# HM_Nightfall-mini-2e_Encoder-PCB-L_v1.net
KiCad netlist of a schematic drawn in EAGLE
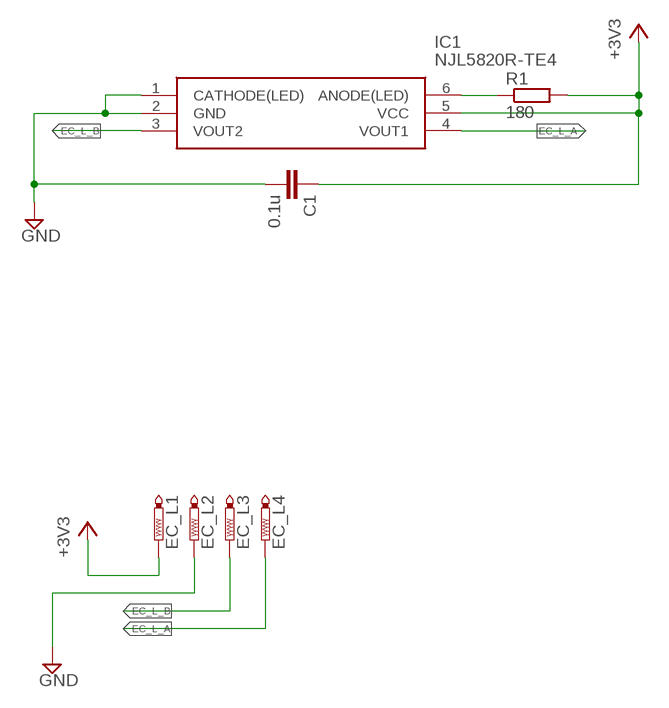
[diagram p0: schematic, sheet 1]

(export (version "E")
  (design (tool "Eeschema 10.0.6"))
  (components
    (comp (ref "C1")
      (value "0.1u")
      (footprint "eagle-import:C0402")
      (libsource (lib "eagle-import") (part "C-EUC0402"))
    )
    (comp (ref "EC_L1")
      (value "PTR1TP06SQ")
      (footprint "eagle-import:TP06SQ")
      (libsource (lib "eagle-import") (part "PTR1TP06SQ"))
    )
    (comp (ref "EC_L2")
      (value "PTR1TP06SQ")
      (footprint "eagle-import:TP06SQ")
      (libsource (lib "eagle-import") (part "PTR1TP06SQ"))
    )
    (comp (ref "EC_L3")
      (value "PTR1TP06SQ")
      (footprint "eagle-import:TP06SQ")
      (libsource (lib "eagle-import") (part "PTR1TP06SQ"))
    )
    (comp (ref "EC_L4")
      (value "PTR1TP06SQ")
      (footprint "eagle-import:TP06SQ")
      (libsource (lib "eagle-import") (part "PTR1TP06SQ"))
    )
    (comp (ref "IC1")
      (value "NJL5820R-TE4")
      (footprint "eagle-import:NJL5820RTE4")
      (fields (field (name "MOUSER_PART_NUMBER") "513-NJL5820R-TE4"))
      (libsource (lib "eagle-import") (part "NJL5820R-TE4"))
    )
    (comp (ref "R1")
      (value "180")
      (footprint "eagle-import:R0402")
      (libsource (lib "eagle-import") (part "R-EU_R0402"))
    )
  )
  (nets
    (net (code "1") (name "+3V3") (class "Default")
      (node (ref "C1") (pin "1") (pinfunction "1_1") (pintype "passive"))
      (node (ref "EC_L1") (pin "TP") (pinfunction "TP_TP") (pintype "input"))
      (node (ref "IC1") (pin "5") (pinfunction "VCC_5") (pintype "bidirectional"))
      (node (ref "R1") (pin "2") (pinfunction "2_2") (pintype "passive"))
    )
    (net (code "2") (name "EC_L_A") (class "Default")
      (node (ref "EC_L4") (pin "TP") (pinfunction "TP_TP") (pintype "input"))
      (node (ref "IC1") (pin "4") (pinfunction "VOUT1_4") (pintype "bidirectional"))
    )
    (net (code "3") (name "EC_L_B") (class "Default")
      (node (ref "EC_L3") (pin "TP") (pinfunction "TP_TP") (pintype "input"))
      (node (ref "IC1") (pin "3") (pinfunction "VOUT2_3") (pintype "bidirectional"))
    )
    (net (code "4") (name "GND") (class "Default")
      (node (ref "C1") (pin "2") (pinfunction "2_2") (pintype "passive"))
      (node (ref "EC_L2") (pin "TP") (pinfunction "TP_TP") (pintype "input"))
      (node (ref "IC1") (pin "1") (pinfunction "CATHODE(LED)_1") (pintype "bidirectional"))
      (node (ref "IC1") (pin "2") (pinfunction "GND_2") (pintype "bidirectional"))
    )
    (net (code "5") (name "Net-(IC1-ANODE(LED))") (class "Default")
      (node (ref "IC1") (pin "6") (pinfunction "ANODE(LED)_6") (pintype "bidirectional"))
      (node (ref "R1") (pin "1") (pinfunction "1_1") (pintype "passive"))
    )
  )
)
